# Candunio.net
KiCad netlist of a schematic drawn in Altium Designer
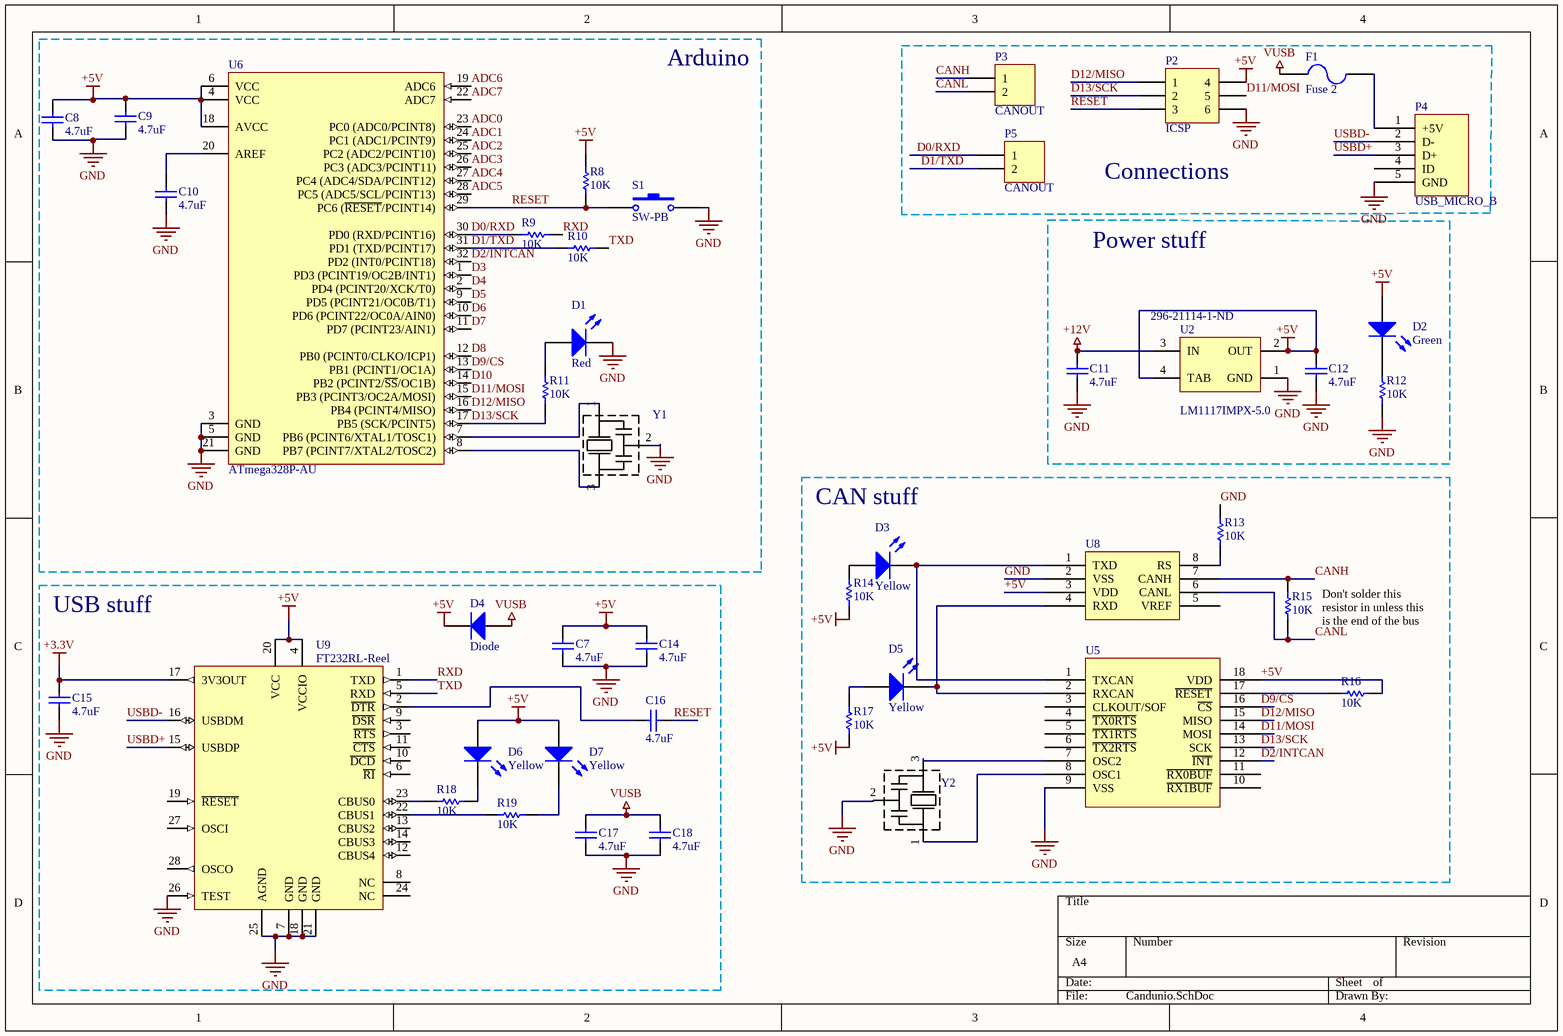
[diagram p0: Candunio.SchDoc]

(export (version "E")
  (design (tool "Eeschema 10.0.6"))
  (components
    (comp (ref "C7")
      (value "4.7uF")
      (footprint "CAPC3216X170N")
      (description "Capacitor (Semiconductor SIM Model)")
      (fields
        (field (name "MANUFACTURER") "Murata")
        (field (name "MANUFACTURER PART NUMBER") "GRM31MR71H105KA88L")
        (field (name "PUBLISHER") "Altium Limited")
      )
      (libsource (lib "Candunio") (part "Cap Semi"))
    )
    (comp (ref "C8")
      (value "4.7uF")
      (footprint "CAPC3216X170N")
      (description "Capacitor (Semiconductor SIM Model)")
      (fields
        (field (name "MANUFACTURER") "Murata")
        (field (name "MANUFACTURER PART NUMBER") "GRM31MR71H105KA88L")
        (field (name "PUBLISHER") "Altium Limited")
      )
      (libsource (lib "Candunio") (part "Cap Semi"))
    )
    (comp (ref "C9")
      (value "4.7uF")
      (footprint "CAPC3216X170N")
      (description "Capacitor (Semiconductor SIM Model)")
      (fields
        (field (name "MANUFACTURER") "Murata")
        (field (name "MANUFACTURER PART NUMBER") "GRM31MR71H105KA88L")
        (field (name "PUBLISHER") "Altium Limited")
      )
      (libsource (lib "Candunio") (part "Cap Semi"))
    )
    (comp (ref "C10")
      (value "4.7uF")
      (footprint "CAPC3216X170N")
      (description "Capacitor (Semiconductor SIM Model)")
      (fields
        (field (name "MANUFACTURER") "Murata")
        (field (name "MANUFACTURER PART NUMBER") "GRM31MR71H105KA88L")
        (field (name "PUBLISHER") "Altium Limited")
      )
      (libsource (lib "Candunio") (part "Cap Semi"))
    )
    (comp (ref "C11")
      (value "4.7uF")
      (footprint "CAPC3216X170N")
      (description "Capacitor (Semiconductor SIM Model)")
      (fields
        (field (name "MANUFACTURER") "Murata")
        (field (name "MANUFACTURER PART NUMBER") "GRM31MR71H105KA88L")
        (field (name "PUBLISHER") "Altium Limited")
      )
      (libsource (lib "Candunio") (part "Cap Semi"))
    )
    (comp (ref "C12")
      (value "4.7uF")
      (footprint "CAPC3216X170N")
      (description "Capacitor (Semiconductor SIM Model)")
      (fields
        (field (name "MANUFACTURER") "Murata")
        (field (name "MANUFACTURER PART NUMBER") "GRM31MR71H105KA88L")
        (field (name "PUBLISHER") "Altium Limited")
      )
      (libsource (lib "Candunio") (part "Cap Semi"))
    )
    (comp (ref "C14")
      (value "4.7uF")
      (footprint "CAPC3216X170N")
      (description "Capacitor (Semiconductor SIM Model)")
      (fields
        (field (name "MANUFACTURER") "Murata")
        (field (name "MANUFACTURER PART NUMBER") "GRM31MR71H105KA88L")
        (field (name "PUBLISHER") "Altium Limited")
      )
      (libsource (lib "Candunio") (part "Cap Semi"))
    )
    (comp (ref "C15")
      (value "4.7uF")
      (footprint "CAPC3216X170N")
      (description "Capacitor (Semiconductor SIM Model)")
      (fields
        (field (name "MANUFACTURER") "Murata")
        (field (name "MANUFACTURER PART NUMBER") "GRM31MR71H105KA88L")
        (field (name "PUBLISHER") "Altium Limited")
      )
      (libsource (lib "Candunio") (part "Cap Semi"))
    )
    (comp (ref "C16")
      (value "4.7uF")
      (footprint "CAPC3216X170N")
      (description "Capacitor (Semiconductor SIM Model)")
      (fields
        (field (name "MANUFACTURER") "Murata")
        (field (name "MANUFACTURER PART NUMBER") "GRM31MR71H105KA88L")
        (field (name "PUBLISHER") "Altium Limited")
      )
      (libsource (lib "Candunio") (part "Cap Semi"))
    )
    (comp (ref "C17")
      (value "4.7uF")
      (footprint "CAPC3216X170N")
      (description "Capacitor (Semiconductor SIM Model)")
      (fields
        (field (name "MANUFACTURER") "Murata")
        (field (name "MANUFACTURER PART NUMBER") "GRM31MR71H105KA88L")
        (field (name "PUBLISHER") "Altium Limited")
      )
      (libsource (lib "Candunio") (part "Cap Semi"))
    )
    (comp (ref "C18")
      (value "4.7uF")
      (footprint "CAPC3216X170N")
      (description "Capacitor (Semiconductor SIM Model)")
      (fields
        (field (name "MANUFACTURER") "Murata")
        (field (name "MANUFACTURER PART NUMBER") "GRM31MR71H105KA88L")
        (field (name "PUBLISHER") "Altium Limited")
      )
      (libsource (lib "Candunio") (part "Cap Semi"))
    )
    (comp (ref "D1")
      (value "Red")
      (footprint "LEDC3216X120NRED")
      (description "Typical RED, GREEN, YELLOW, AMBER GaAs LED")
      (fields
        (field (name "MANUFACTURER") "Broadcom Avago")
        (field (name "MANUFACTURER PART NUMBER") "HSMY-C150")
        (field (name "PUBLISHER") "Altium Limited")
      )
      (libsource (lib "Candunio") (part "LED2_2"))
    )
    (comp (ref "D2")
      (value "Green")
      (footprint "LEDC3216X120NGRN")
      (description "Typical RED, GREEN, YELLOW, AMBER GaAs LED")
      (fields
        (field (name "MANUFACTURER") "Broadcom Avago")
        (field (name "MANUFACTURER PART NUMBER") "HSMG-C150")
        (field (name "PUBLISHER") "Altium Limited")
      )
      (libsource (lib "Candunio") (part "LED2"))
    )
    (comp (ref "D3")
      (value "Yellow")
      (footprint "LEDC3216X120NYEL")
      (description "Typical RED, GREEN, YELLOW, AMBER GaAs LED")
      (fields
        (field (name "MANUFACTURER") "Broadcom Avago")
        (field (name "MANUFACTURER PART NUMBER") "HSMY-C150")
        (field (name "PUBLISHER") "Altium Limited")
      )
      (libsource (lib "Candunio") (part "LED2_1"))
    )
    (comp (ref "D4")
      (value "Diode")
      (footprint "DO-220AA")
      (description "Default Diode")
      (fields (field (name "PUBLISHER") "Altium Limited"))
      (libsource (lib "Candunio") (part "Diode"))
    )
    (comp (ref "D5")
      (value "Yellow")
      (footprint "LEDC3216X120NYEL")
      (description "Typical RED, GREEN, YELLOW, AMBER GaAs LED")
      (fields
        (field (name "MANUFACTURER") "Broadcom Avago")
        (field (name "MANUFACTURER PART NUMBER") "HSMY-C150")
        (field (name "PUBLISHER") "Altium Limited")
      )
      (libsource (lib "Candunio") (part "LED2_1"))
    )
    (comp (ref "D6")
      (value "Yellow")
      (footprint "LEDC3216X120NYEL")
      (description "Typical RED, GREEN, YELLOW, AMBER GaAs LED")
      (fields
        (field (name "MANUFACTURER") "Broadcom Avago")
        (field (name "MANUFACTURER PART NUMBER") "HSMY-C150")
        (field (name "PUBLISHER") "Altium Limited")
      )
      (libsource (lib "Candunio") (part "LED2_1"))
    )
    (comp (ref "D7")
      (value "Yellow")
      (footprint "LEDC3216X120NYEL")
      (description "Typical RED, GREEN, YELLOW, AMBER GaAs LED")
      (fields
        (field (name "MANUFACTURER") "Broadcom Avago")
        (field (name "MANUFACTURER PART NUMBER") "HSMY-C150")
        (field (name "PUBLISHER") "Altium Limited")
      )
      (libsource (lib "Candunio") (part "LED2_1"))
    )
    (comp (ref "F1")
      (value "Fuse 2")
      (footprint "FUSC4632X85N")
      (description "Fuse")
      (fields
        (field (name "PART NUMBER") "MF-MSMF050-2")
        (field (name "MANUFACTURER") "Bourns")
        (field (name "PUBLISHER") "Altium Limited")
      )
      (libsource (lib "Candunio") (part "Fuse 2"))
    )
    (comp (ref "P2")
      (value "ICSP")
      (footprint "Pin Header 2x3 TH Pitch 2.54mm")
      (description "Header, 3-Pin, Dual row")
      (fields (field (name "PUBLISHER") "Altium Limited"))
      (libsource (lib "Candunio") (part "Header 3X2A"))
    )
    (comp (ref "P3")
      (value "CANOUT")
      (footprint "Pin Header 1x2 TH Pitch 2.54mm")
      (description "Header, 2-Pin")
      (fields (field (name "PUBLISHER") "Altium Limited"))
      (libsource (lib "Candunio") (part "Header 2"))
    )
    (comp (ref "P4")
      (value "USB_MICRO_B")
      (footprint "USB MICRO B THRU")
      (libsource (lib "400ETB_SchematicLib") (part "USB_MICRO_B"))
    )
    (comp (ref "P5")
      (value "CANOUT")
      (footprint "Pin Header 1x2 TH Pitch 2.54mm")
      (description "Header, 2-Pin")
      (fields (field (name "PUBLISHER") "Altium Limited"))
      (libsource (lib "Candunio") (part "Header 2"))
    )
    (comp (ref "R8")
      (value "10K")
      (footprint "RESC3216X60N")
      (description "Resistor")
      (fields
        (field (name "MANUFACTURER") "Stackpole Electronics")
        (field (name "MANUFACTURER PART NUMBER") "RNCP1206FTD1K00")
      )
      (libsource (lib "Candunio") (part "Res1"))
    )
    (comp (ref "R9")
      (value "10K")
      (footprint "RESC3216X60N")
      (description "Resistor")
      (fields
        (field (name "MANUFACTURER") "Stackpole Electronics")
        (field (name "MANUFACTURER PART NUMBER") "RNCP1206FTD1K00")
      )
      (libsource (lib "Candunio") (part "Res1"))
    )
    (comp (ref "R10")
      (value "10K")
      (footprint "RESC3216X60N")
      (description "Resistor")
      (fields
        (field (name "MANUFACTURER") "Stackpole Electronics")
        (field (name "MANUFACTURER PART NUMBER") "RNCP1206FTD1K00")
      )
      (libsource (lib "Candunio") (part "Res1"))
    )
    (comp (ref "R11")
      (value "10K")
      (footprint "RESC3216X60N")
      (description "Resistor")
      (fields
        (field (name "MANUFACTURER") "Stackpole Electronics")
        (field (name "MANUFACTURER PART NUMBER") "RNCP1206FTD1K00")
      )
      (libsource (lib "Candunio") (part "Res1"))
    )
    (comp (ref "R12")
      (value "10K")
      (footprint "RESC3216X60N")
      (description "Resistor")
      (fields
        (field (name "MANUFACTURER") "Stackpole Electronics")
        (field (name "MANUFACTURER PART NUMBER") "RNCP1206FTD1K00")
      )
      (libsource (lib "Candunio") (part "Res1"))
    )
    (comp (ref "R13")
      (value "10K")
      (footprint "RESC3216X60N")
      (description "Resistor")
      (fields
        (field (name "MANUFACTURER") "Stackpole Electronics")
        (field (name "MANUFACTURER PART NUMBER") "RNCP1206FTD1K00")
      )
      (libsource (lib "Candunio") (part "Res1"))
    )
    (comp (ref "R14")
      (value "10K")
      (footprint "RESC3216X60N")
      (description "Resistor")
      (fields
        (field (name "MANUFACTURER") "Stackpole Electronics")
        (field (name "MANUFACTURER PART NUMBER") "RNCP1206FTD1K00")
      )
      (libsource (lib "Candunio") (part "Res1"))
    )
    (comp (ref "R15")
      (value "10K")
      (footprint "RESC3216X60N")
      (description "Resistor")
      (fields
        (field (name "MANUFACTURER") "Stackpole Electronics")
        (field (name "MANUFACTURER PART NUMBER") "RNCP1206FTD1K00")
      )
      (libsource (lib "Candunio") (part "Res1"))
    )
    (comp (ref "R16")
      (value "10K")
      (footprint "RESC3216X60N")
      (description "Resistor")
      (fields
        (field (name "MANUFACTURER") "Stackpole Electronics")
        (field (name "MANUFACTURER PART NUMBER") "RNCP1206FTD1K00")
      )
      (libsource (lib "Candunio") (part "Res1"))
    )
    (comp (ref "R17")
      (value "10K")
      (footprint "RESC3216X60N")
      (description "Resistor")
      (fields
        (field (name "MANUFACTURER") "Stackpole Electronics")
        (field (name "MANUFACTURER PART NUMBER") "RNCP1206FTD1K00")
      )
      (libsource (lib "Candunio") (part "Res1"))
    )
    (comp (ref "R18")
      (value "10K")
      (footprint "RESC3216X60N")
      (description "Resistor")
      (fields
        (field (name "MANUFACTURER") "Stackpole Electronics")
        (field (name "MANUFACTURER PART NUMBER") "RNCP1206FTD1K00")
      )
      (libsource (lib "Candunio") (part "Res1"))
    )
    (comp (ref "R19")
      (value "10K")
      (footprint "RESC3216X60N")
      (description "Resistor")
      (fields
        (field (name "MANUFACTURER") "Stackpole Electronics")
        (field (name "MANUFACTURER PART NUMBER") "RNCP1206FTD1K00")
      )
      (libsource (lib "Candunio") (part "Res1"))
    )
    (comp (ref "S1")
      (value "SW-PB")
      (footprint "SMDswitch_1206")
      (description "Switch")
      (fields
        (field (name "MANUFACTURER") "ITT C&K")
        (field (name "MANUFACTURER PART NUMBER") "KXT331LHS")
        (field (name "PUBLISHER") "Altium Limited")
      )
      (libsource (lib "Candunio") (part "SW-PB"))
    )
    (comp (ref "U2")
      (value "LM1117IMPX-5.0")
      (footprint "SOT230P700X180-4N")
      (description "800mA Low-Dropout Linear Regulator, 4-pin SOT-223")
      (fields
        (field (name "PARTNUMBER") "LM1117IMPX-5.0/NOPBCT-ND")
        (field (name "MANUFACTURER") "National Semiconductor")
        (field (name "SUPPLIER PART NUMBER") "296-21114-1-ND")
        (field (name "PUBLISHER") "Altium Limited")
      )
      (libsource (lib "NSC LDO") (part "LM1117IMPX-5.0"))
    )
    (comp (ref "U5")
      (value "MCP2515-E/ST")
      (footprint "SOIC127P1030X265-18N")
      (description "SOIC")
      (libsource (lib "Candunio") (part "MCP2515-E/ST"))
    )
    (comp (ref "U6")
      (value "ATmega328P-AU")
      (footprint "QFP80P900X900X120-32N")
      (fields (field (name "PUBLISHER") "Altium Limited"))
      (libsource (lib "Candunio") (part "ATmega328P-AU"))
    )
    (comp (ref "U8")
      (value "MCP2551-E/SN")
      (footprint "SOIC127P600X175-8N")
      (description "SOIC")
      (libsource (lib "Candunio") (part "MCP2551-E/SN"))
    )
    (comp (ref "U9")
      (value "FT232RL-Reel")
      (footprint "SOP65P780X200-28N")
      (description "USB UART Asynchronous Serial Data Transfer Chip, SSOP-28, Tape and Reel")
      (fields
        (field (name "MANUFACTURER") "FTDI")
        (field (name "MANUFACTURER PART NUMBER") "FT232RL-REEL")
        (field (name "PUBLISHER") "Altium Limited")
      )
      (libsource (lib "FTDI Communication UART") (part "FT232RL-Reel"))
    )
    (comp (ref "Y1")
      (value "CSTCE16M0V53-R0")
      (footprint "CSTCE_G")
      (fields
        (field (name "MANUFACTURER") "Murata")
        (field (name "MANUFACTURER PART NUMBER") "CSTCE16M0V53C-R0")
        (field (name "TOLERANCE") "0.5%")
      )
      (libsource (lib "Candunio") (part "CSTCE16M0V53-R0"))
    )
    (comp (ref "Y2")
      (value "CSTCE16M0V53-R0")
      (footprint "CSTCE_G")
      (fields
        (field (name "MANUFACTURER") "Murata")
        (field (name "MANUFACTURER PART NUMBER") "CSTCE16M0V53C-R0")
        (field (name "TOLERANCE") "0.5%")
      )
      (libsource (lib "Candunio") (part "CSTCE16M0V53-R0"))
    )
  )
  (nets
    (net (code "1") (name "+3.3V") (class "Default")
      (node (ref "C15") (pin "2") (pinfunction "2_2") (pintype "passive"))
      (node (ref "U9") (pin "17") (pinfunction "3V3OUT_17") (pintype "output"))
    )
    (net (code "2") (name "+5V") (class "Default")
      (node (ref "C12") (pin "2") (pinfunction "2_2") (pintype "passive"))
      (node (ref "C14") (pin "2") (pinfunction "2_2") (pintype "passive"))
      (node (ref "C7") (pin "2") (pinfunction "2_2") (pintype "passive"))
      (node (ref "C8") (pin "1") (pinfunction "1_1") (pintype "passive"))
      (node (ref "C9") (pin "2") (pinfunction "2_2") (pintype "passive"))
      (node (ref "D2") (pin "1") (pinfunction "A_1") (pintype "passive"))
      (node (ref "D4") (pin "2") (pinfunction "K_2") (pintype "passive"))
      (node (ref "D6") (pin "1") (pinfunction "A_1") (pintype "passive"))
      (node (ref "D7") (pin "1") (pinfunction "A_1") (pintype "passive"))
      (node (ref "P2") (pin "4") (pinfunction "4_4") (pintype "passive"))
      (node (ref "R14") (pin "1") (pinfunction "1_1") (pintype "passive"))
      (node (ref "R16") (pin "2") (pinfunction "2_2") (pintype "passive"))
      (node (ref "R17") (pin "2") (pinfunction "2_2") (pintype "passive"))
      (node (ref "R8") (pin "1") (pinfunction "1_1") (pintype "passive"))
      (node (ref "U2") (pin "2") (pinfunction "OUT_2") (pintype "power_in"))
      (node (ref "U2") (pin "4") (pinfunction "TAB_4") (pintype "power_in"))
      (node (ref "U5") (pin "18") (pinfunction "VDD_18") (pintype "passive"))
      (node (ref "U6") (pin "18") (pinfunction "AVCC_18") (pintype "power_in"))
      (node (ref "U6") (pin "4") (pinfunction "VCC_4") (pintype "power_in"))
      (node (ref "U6") (pin "6") (pinfunction "VCC_6") (pintype "power_in"))
      (node (ref "U8") (pin "3") (pinfunction "VDD_3") (pintype "passive"))
      (node (ref "U9") (pin "20") (pinfunction "VCC_20") (pintype "power_in"))
      (node (ref "U9") (pin "4") (pinfunction "VCCIO_4") (pintype "power_in"))
    )
    (net (code "3") (name "+12V") (class "Default")
      (node (ref "C11") (pin "2") (pinfunction "2_2") (pintype "passive"))
      (node (ref "U2") (pin "3") (pinfunction "IN_3") (pintype "power_in"))
    )
    (net (code "4") (name "/ADC0") (class "Default")
      (node (ref "U6") (pin "23") (pinfunction "PC0_(ADC0/PCINT8)_23") (pintype "bidirectional"))
    )
    (net (code "5") (name "/ADC1") (class "Default")
      (node (ref "U6") (pin "24") (pinfunction "PC1_(ADC1/PCINT9)_24") (pintype "bidirectional"))
    )
    (net (code "6") (name "/ADC2") (class "Default")
      (node (ref "U6") (pin "25") (pinfunction "PC2_(ADC2/PCINT10)_25") (pintype "bidirectional"))
    )
    (net (code "7") (name "/ADC3") (class "Default")
      (node (ref "U6") (pin "26") (pinfunction "PC3_(ADC3/PCINT11)_26") (pintype "bidirectional"))
    )
    (net (code "8") (name "/ADC4") (class "Default")
      (node (ref "U6") (pin "27") (pinfunction "PC4_(ADC4/SDA/PCINT12)_27") (pintype "bidirectional"))
    )
    (net (code "9") (name "/ADC5") (class "Default")
      (node (ref "U6") (pin "28") (pinfunction "PC5_(ADC5/SCL/PCINT13)_28") (pintype "bidirectional"))
    )
    (net (code "10") (name "/ADC6") (class "Default")
      (node (ref "U6") (pin "19") (pinfunction "ADC6_19") (pintype "input"))
    )
    (net (code "11") (name "/ADC7") (class "Default")
      (node (ref "U6") (pin "22") (pinfunction "ADC7_22") (pintype "input"))
    )
    (net (code "12") (name "/CANH") (class "Default")
      (node (ref "P3") (pin "1") (pinfunction "1_1") (pintype "passive"))
      (node (ref "R15") (pin "1") (pinfunction "1_1") (pintype "passive"))
      (node (ref "U8") (pin "7") (pinfunction "CANH_7") (pintype "passive"))
    )
    (net (code "13") (name "/CANL") (class "Default")
      (node (ref "P3") (pin "2") (pinfunction "2_2") (pintype "passive"))
      (node (ref "R15") (pin "2") (pinfunction "2_2") (pintype "passive"))
      (node (ref "U8") (pin "6") (pinfunction "CANL_6") (pintype "passive"))
    )
    (net (code "14") (name "/D0{slash}RXD") (class "Default")
      (node (ref "P5") (pin "1") (pinfunction "1_1") (pintype "passive"))
      (node (ref "R9") (pin "1") (pinfunction "1_1") (pintype "passive"))
      (node (ref "U6") (pin "30") (pinfunction "PD0_(RXD/PCINT16)_30") (pintype "bidirectional"))
    )
    (net (code "15") (name "/D1{slash}TXD") (class "Default")
      (node (ref "P5") (pin "2") (pinfunction "2_2") (pintype "passive"))
      (node (ref "R10") (pin "1") (pinfunction "1_1") (pintype "passive"))
      (node (ref "U6") (pin "31") (pinfunction "PD1_(TXD/PCINT17)_31") (pintype "bidirectional"))
    )
    (net (code "16") (name "/D2{slash}INTCAN") (class "Default")
      (node (ref "U5") (pin "12") (pinfunction "~{INT}_12") (pintype "passive"))
      (node (ref "U6") (pin "32") (pinfunction "PD2_(INT0/PCINT18)_32") (pintype "bidirectional"))
    )
    (net (code "17") (name "/D3") (class "Default")
      (node (ref "U6") (pin "1") (pinfunction "PD3_(PCINT19/OC2B/INT1)_1") (pintype "bidirectional"))
    )
    (net (code "18") (name "/D4") (class "Default")
      (node (ref "U6") (pin "2") (pinfunction "PD4_(PCINT20/XCK/T0)_2") (pintype "bidirectional"))
    )
    (net (code "19") (name "/D5") (class "Default")
      (node (ref "U6") (pin "9") (pinfunction "PD5_(PCINT21/OC0B/T1)_9") (pintype "bidirectional"))
    )
    (net (code "20") (name "/D6") (class "Default")
      (node (ref "U6") (pin "10") (pinfunction "PD6_(PCINT22/OC0A/AIN0)_10") (pintype "bidirectional"))
    )
    (net (code "21") (name "/D7") (class "Default")
      (node (ref "U6") (pin "11") (pinfunction "PD7_(PCINT23/AIN1)_11") (pintype "bidirectional"))
    )
    (net (code "22") (name "/D8") (class "Default")
      (node (ref "U6") (pin "12") (pinfunction "PB0_(PCINT0/CLKO/ICP1)_12") (pintype "bidirectional"))
    )
    (net (code "23") (name "/D9{slash}CS") (class "Default")
      (node (ref "U5") (pin "16") (pinfunction "~{CS}_16") (pintype "passive"))
      (node (ref "U6") (pin "13") (pinfunction "PB1_(PCINT1/OC1A)_13") (pintype "bidirectional"))
    )
    (net (code "24") (name "/D10") (class "Default")
      (node (ref "U6") (pin "14") (pinfunction "PB2_(PCINT2/~{SS}/OC1B)_14") (pintype "bidirectional"))
    )
    (net (code "25") (name "/D11{slash}MOSI") (class "Default")
      (node (ref "P2") (pin "5") (pinfunction "5_5") (pintype "passive"))
      (node (ref "U5") (pin "14") (pinfunction "MOSI_14") (pintype "passive"))
      (node (ref "U6") (pin "15") (pinfunction "PB3_(PCINT3/OC2A/MOSI)_15") (pintype "bidirectional"))
    )
    (net (code "26") (name "/D12{slash}MISO") (class "Default")
      (node (ref "P2") (pin "1") (pinfunction "1_1") (pintype "passive"))
      (node (ref "U5") (pin "15") (pinfunction "MISO_15") (pintype "passive"))
      (node (ref "U6") (pin "16") (pinfunction "PB4_(PCINT4/MISO)_16") (pintype "bidirectional"))
    )
    (net (code "27") (name "/D13{slash}SCK") (class "Default")
      (node (ref "P2") (pin "2") (pinfunction "2_2") (pintype "passive"))
      (node (ref "R11") (pin "2") (pinfunction "2_2") (pintype "passive"))
      (node (ref "U5") (pin "13") (pinfunction "SCK_13") (pintype "passive"))
      (node (ref "U6") (pin "17") (pinfunction "PB5_(SCK/PCINT5)_17") (pintype "bidirectional"))
    )
    (net (code "28") (name "/RESET") (class "Default")
      (node (ref "C16") (pin "2") (pinfunction "2_2") (pintype "passive"))
      (node (ref "P2") (pin "3") (pinfunction "3_3") (pintype "passive"))
      (node (ref "R8") (pin "2") (pinfunction "2_2") (pintype "passive"))
      (node (ref "S1") (pin "1") (pinfunction "1_1") (pintype "passive"))
      (node (ref "U6") (pin "29") (pinfunction "PC6_(~{RESET}/PCINT14)_29") (pintype "bidirectional"))
    )
    (net (code "29") (name "/RXD") (class "Default")
      (node (ref "R9") (pin "2") (pinfunction "2_2") (pintype "passive"))
      (node (ref "U9") (pin "1") (pinfunction "TXD_1") (pintype "output"))
    )
    (net (code "30") (name "/TXD") (class "Default")
      (node (ref "R10") (pin "2") (pinfunction "2_2") (pintype "passive"))
      (node (ref "U9") (pin "5") (pinfunction "RXD_5") (pintype "input"))
    )
    (net (code "31") (name "/USBD+") (class "Default")
      (node (ref "P4") (pin "3") (pinfunction "D+_3") (pintype "passive"))
      (node (ref "U9") (pin "15") (pinfunction "USBDP_15") (pintype "bidirectional"))
    )
    (net (code "32") (name "/USBD-") (class "Default")
      (node (ref "P4") (pin "2") (pinfunction "D-_2") (pintype "passive"))
      (node (ref "U9") (pin "16") (pinfunction "USBDM_16") (pintype "bidirectional"))
    )
    (net (code "33") (name "GND") (class "Default")
      (node (ref "C10") (pin "1") (pinfunction "1_1") (pintype "passive"))
      (node (ref "C11") (pin "1") (pinfunction "1_1") (pintype "passive"))
      (node (ref "C12") (pin "1") (pinfunction "1_1") (pintype "passive"))
      (node (ref "C14") (pin "1") (pinfunction "1_1") (pintype "passive"))
      (node (ref "C15") (pin "1") (pinfunction "1_1") (pintype "passive"))
      (node (ref "C17") (pin "1") (pinfunction "1_1") (pintype "passive"))
      (node (ref "C18") (pin "1") (pinfunction "1_1") (pintype "passive"))
      (node (ref "C7") (pin "1") (pinfunction "1_1") (pintype "passive"))
      (node (ref "C8") (pin "2") (pinfunction "2_2") (pintype "passive"))
      (node (ref "C9") (pin "1") (pinfunction "1_1") (pintype "passive"))
      (node (ref "D1") (pin "2") (pinfunction "K_2") (pintype "passive"))
      (node (ref "P2") (pin "6") (pinfunction "6_6") (pintype "passive"))
      (node (ref "P4") (pin "5") (pinfunction "GND_5") (pintype "passive"))
      (node (ref "R12") (pin "2") (pinfunction "2_2") (pintype "passive"))
      (node (ref "R13") (pin "1") (pinfunction "1_1") (pintype "passive"))
      (node (ref "S1") (pin "2") (pinfunction "2_2") (pintype "passive"))
      (node (ref "U2") (pin "1") (pinfunction "GND_1") (pintype "power_in"))
      (node (ref "U5") (pin "9") (pinfunction "VSS_9") (pintype "passive"))
      (node (ref "U6") (pin "21") (pinfunction "GND_21") (pintype "power_in"))
      (node (ref "U6") (pin "3") (pinfunction "GND_3") (pintype "power_in"))
      (node (ref "U6") (pin "5") (pinfunction "GND_5") (pintype "power_in"))
      (node (ref "U8") (pin "2") (pinfunction "VSS_2") (pintype "passive"))
      (node (ref "U9") (pin "18") (pinfunction "GND_18") (pintype "power_in"))
      (node (ref "U9") (pin "21") (pinfunction "GND_21") (pintype "power_in"))
      (node (ref "U9") (pin "25") (pinfunction "AGND_25") (pintype "power_in"))
      (node (ref "U9") (pin "26") (pinfunction "TEST_26") (pintype "input"))
      (node (ref "U9") (pin "7") (pinfunction "GND_7") (pintype "power_in"))
      (node (ref "Y1") (pin "2") (pinfunction "2_2") (pintype "passive"))
      (node (ref "Y2") (pin "2") (pinfunction "2_2") (pintype "passive"))
    )
    (net (code "34") (name "Net-(D1-A)") (class "Default")
      (node (ref "D1") (pin "1") (pinfunction "A_1") (pintype "passive"))
      (node (ref "R11") (pin "1") (pinfunction "1_1") (pintype "passive"))
    )
    (net (code "35") (name "Net-(D2-K)") (class "Default")
      (node (ref "D2") (pin "2") (pinfunction "K_2") (pintype "passive"))
      (node (ref "R12") (pin "1") (pinfunction "1_1") (pintype "passive"))
    )
    (net (code "36") (name "Net-(D3-A)") (class "Default")
      (node (ref "D3") (pin "1") (pinfunction "A_1") (pintype "passive"))
      (node (ref "R14") (pin "2") (pinfunction "2_2") (pintype "passive"))
    )
    (net (code "37") (name "Net-(D3-K)") (class "Default")
      (node (ref "D3") (pin "2") (pinfunction "K_2") (pintype "passive"))
      (node (ref "U5") (pin "1") (pinfunction "TXCAN_1") (pintype "passive"))
      (node (ref "U8") (pin "1") (pinfunction "TXD_1") (pintype "passive"))
    )
    (net (code "38") (name "Net-(D5-A)") (class "Default")
      (node (ref "D5") (pin "1") (pinfunction "A_1") (pintype "passive"))
      (node (ref "R17") (pin "1") (pinfunction "1_1") (pintype "passive"))
    )
    (net (code "39") (name "Net-(D5-K)") (class "Default")
      (node (ref "D5") (pin "2") (pinfunction "K_2") (pintype "passive"))
      (node (ref "U5") (pin "2") (pinfunction "RXCAN_2") (pintype "passive"))
      (node (ref "U8") (pin "4") (pinfunction "RXD_4") (pintype "passive"))
    )
    (net (code "40") (name "Net-(D6-K)") (class "Default")
      (node (ref "D6") (pin "2") (pinfunction "K_2") (pintype "passive"))
      (node (ref "R18") (pin "2") (pinfunction "2_2") (pintype "passive"))
    )
    (net (code "41") (name "Net-(D7-K)") (class "Default")
      (node (ref "D7") (pin "2") (pinfunction "K_2") (pintype "passive"))
      (node (ref "R19") (pin "2") (pinfunction "2_2") (pintype "passive"))
    )
    (net (code "42") (name "Net-(P4-+5V)") (class "Default")
      (node (ref "F1") (pin "2") (pinfunction "2_2") (pintype "passive"))
      (node (ref "P4") (pin "1") (pinfunction "+5V_1") (pintype "passive"))
    )
    (net (code "43") (name "Net-(U5-OSC1)") (class "Default")
      (node (ref "U5") (pin "8") (pinfunction "OSC1_8") (pintype "passive"))
      (node (ref "Y2") (pin "1") (pinfunction "1_1") (pintype "passive"))
    )
    (net (code "44") (name "Net-(U5-OSC2)") (class "Default")
      (node (ref "U5") (pin "7") (pinfunction "OSC2_7") (pintype "passive"))
      (node (ref "Y2") (pin "3") (pinfunction "3_3") (pintype "passive"))
    )
    (net (code "45") (name "Net-(U5-~{RESET})") (class "Default")
      (node (ref "R16") (pin "1") (pinfunction "1_1") (pintype "passive"))
      (node (ref "U5") (pin "17") (pinfunction "~{RESET}_17") (pintype "passive"))
    )
    (net (code "46") (name "Net-(U6-AREF)") (class "Default")
      (node (ref "C10") (pin "2") (pinfunction "2_2") (pintype "passive"))
      (node (ref "U6") (pin "20") (pinfunction "AREF_20") (pintype "passive"))
    )
    (net (code "47") (name "Net-(U6-PB6_(PCINT6{slash}XTAL1{slash}TOSC1))") (class "Default")
      (node (ref "U6") (pin "7") (pinfunction "PB6_(PCINT6/XTAL1/TOSC1)_7") (pintype "bidirectional"))
      (node (ref "Y1") (pin "1") (pinfunction "1_1") (pintype "passive"))
    )
    (net (code "48") (name "Net-(U6-PB7_(PCINT7{slash}XTAL2{slash}TOSC2))") (class "Default")
      (node (ref "U6") (pin "8") (pinfunction "PB7_(PCINT7/XTAL2/TOSC2)_8") (pintype "bidirectional"))
      (node (ref "Y1") (pin "3") (pinfunction "3_3") (pintype "passive"))
    )
    (net (code "49") (name "Net-(U8-RS)") (class "Default")
      (node (ref "R13") (pin "2") (pinfunction "2_2") (pintype "passive"))
      (node (ref "U8") (pin "8") (pinfunction "RS_8") (pintype "passive"))
    )
    (net (code "50") (name "Net-(U9-CBUS0)") (class "Default")
      (node (ref "R18") (pin "1") (pinfunction "1_1") (pintype "passive"))
      (node (ref "U9") (pin "23") (pinfunction "CBUS0_23") (pintype "bidirectional"))
    )
    (net (code "51") (name "Net-(U9-CBUS1)") (class "Default")
      (node (ref "R19") (pin "1") (pinfunction "1_1") (pintype "passive"))
      (node (ref "U9") (pin "22") (pinfunction "CBUS1_22") (pintype "bidirectional"))
    )
    (net (code "52") (name "Net-(U9-~{DTR})") (class "Default")
      (node (ref "C16") (pin "1") (pinfunction "1_1") (pintype "passive"))
      (node (ref "U9") (pin "2") (pinfunction "~{DTR}_2") (pintype "output"))
    )
    (net (code "53") (name "VUSB") (class "Default")
      (node (ref "C17") (pin "2") (pinfunction "2_2") (pintype "passive"))
      (node (ref "C18") (pin "2") (pinfunction "2_2") (pintype "passive"))
      (node (ref "D4") (pin "1") (pinfunction "A_1") (pintype "passive"))
      (node (ref "F1") (pin "1") (pinfunction "1_1") (pintype "passive"))
    )
    (net (code "54") (name "unconnected-(P4-ID-Pad4)") (class "Default")
      (node (ref "P4") (pin "4") (pinfunction "ID_4") (pintype "passive"))
    )
    (net (code "55") (name "unconnected-(U5-CLKOUT{slash}SOF-Pad3)") (class "Default")
      (node (ref "U5") (pin "3") (pinfunction "CLKOUT/SOF_3") (pintype "passive"))
    )
    (net (code "56") (name "unconnected-(U5-~{RX0BUF}-Pad11)") (class "Default")
      (node (ref "U5") (pin "11") (pinfunction "~{RX0BUF}_11") (pintype "passive"))
    )
    (net (code "57") (name "unconnected-(U5-~{RX1BUF}-Pad10)") (class "Default")
      (node (ref "U5") (pin "10") (pinfunction "~{RX1BUF}_10") (pintype "passive"))
    )
    (net (code "58") (name "unconnected-(U5-~{TX0RTS}-Pad4)") (class "Default")
      (node (ref "U5") (pin "4") (pinfunction "~{TX0RTS}_4") (pintype "passive"))
    )
    (net (code "59") (name "unconnected-(U5-~{TX1RTS}-Pad5)") (class "Default")
      (node (ref "U5") (pin "5") (pinfunction "~{TX1RTS}_5") (pintype "passive"))
    )
    (net (code "60") (name "unconnected-(U5-~{TX2RTS}-Pad6)") (class "Default")
      (node (ref "U5") (pin "6") (pinfunction "~{TX2RTS}_6") (pintype "passive"))
    )
    (net (code "61") (name "unconnected-(U8-VREF-Pad5)") (class "Default")
      (node (ref "U8") (pin "5") (pinfunction "VREF_5") (pintype "passive"))
    )
    (net (code "62") (name "unconnected-(U9-CBUS2-Pad13)") (class "Default")
      (node (ref "U9") (pin "13") (pinfunction "CBUS2_13") (pintype "bidirectional"))
    )
    (net (code "63") (name "unconnected-(U9-CBUS3-Pad14)") (class "Default")
      (node (ref "U9") (pin "14") (pinfunction "CBUS3_14") (pintype "bidirectional"))
    )
    (net (code "64") (name "unconnected-(U9-CBUS4-Pad12)") (class "Default")
      (node (ref "U9") (pin "12") (pinfunction "CBUS4_12") (pintype "bidirectional"))
    )
    (net (code "65") (name "unconnected-(U9-NC-Pad8)") (class "Default")
      (node (ref "U9") (pin "8") (pinfunction "NC_8") (pintype "passive"))
    )
    (net (code "66") (name "unconnected-(U9-NC-Pad24)") (class "Default")
      (node (ref "U9") (pin "24") (pinfunction "NC_24") (pintype "passive"))
    )
    (net (code "67") (name "unconnected-(U9-OSCI-Pad27)") (class "Default")
      (node (ref "U9") (pin "27") (pinfunction "OSCI_27") (pintype "input"))
    )
    (net (code "68") (name "unconnected-(U9-OSCO-Pad28)") (class "Default")
      (node (ref "U9") (pin "28") (pinfunction "OSCO_28") (pintype "output"))
    )
    (net (code "69") (name "unconnected-(U9-~{CTS}-Pad11)") (class "Default")
      (node (ref "U9") (pin "11") (pinfunction "~{CTS}_11") (pintype "input"))
    )
    (net (code "70") (name "unconnected-(U9-~{DCD}-Pad10)") (class "Default")
      (node (ref "U9") (pin "10") (pinfunction "~{DCD}_10") (pintype "input"))
    )
    (net (code "71") (name "unconnected-(U9-~{DSR}-Pad9)") (class "Default")
      (node (ref "U9") (pin "9") (pinfunction "~{DSR}_9") (pintype "input"))
    )
    (net (code "72") (name "unconnected-(U9-~{RESET}-Pad19)") (class "Default")
      (node (ref "U9") (pin "19") (pinfunction "~{RESET}_19") (pintype "input"))
    )
    (net (code "73") (name "unconnected-(U9-~{RI}-Pad6)") (class "Default")
      (node (ref "U9") (pin "6") (pinfunction "~{RI}_6") (pintype "input"))
    )
    (net (code "74") (name "unconnected-(U9-~{RTS}-Pad3)") (class "Default")
      (node (ref "U9") (pin "3") (pinfunction "~{RTS}_3") (pintype "output"))
    )
  )
)
